# Sch.net
KiCad netlist of a schematic drawn in EAGLE
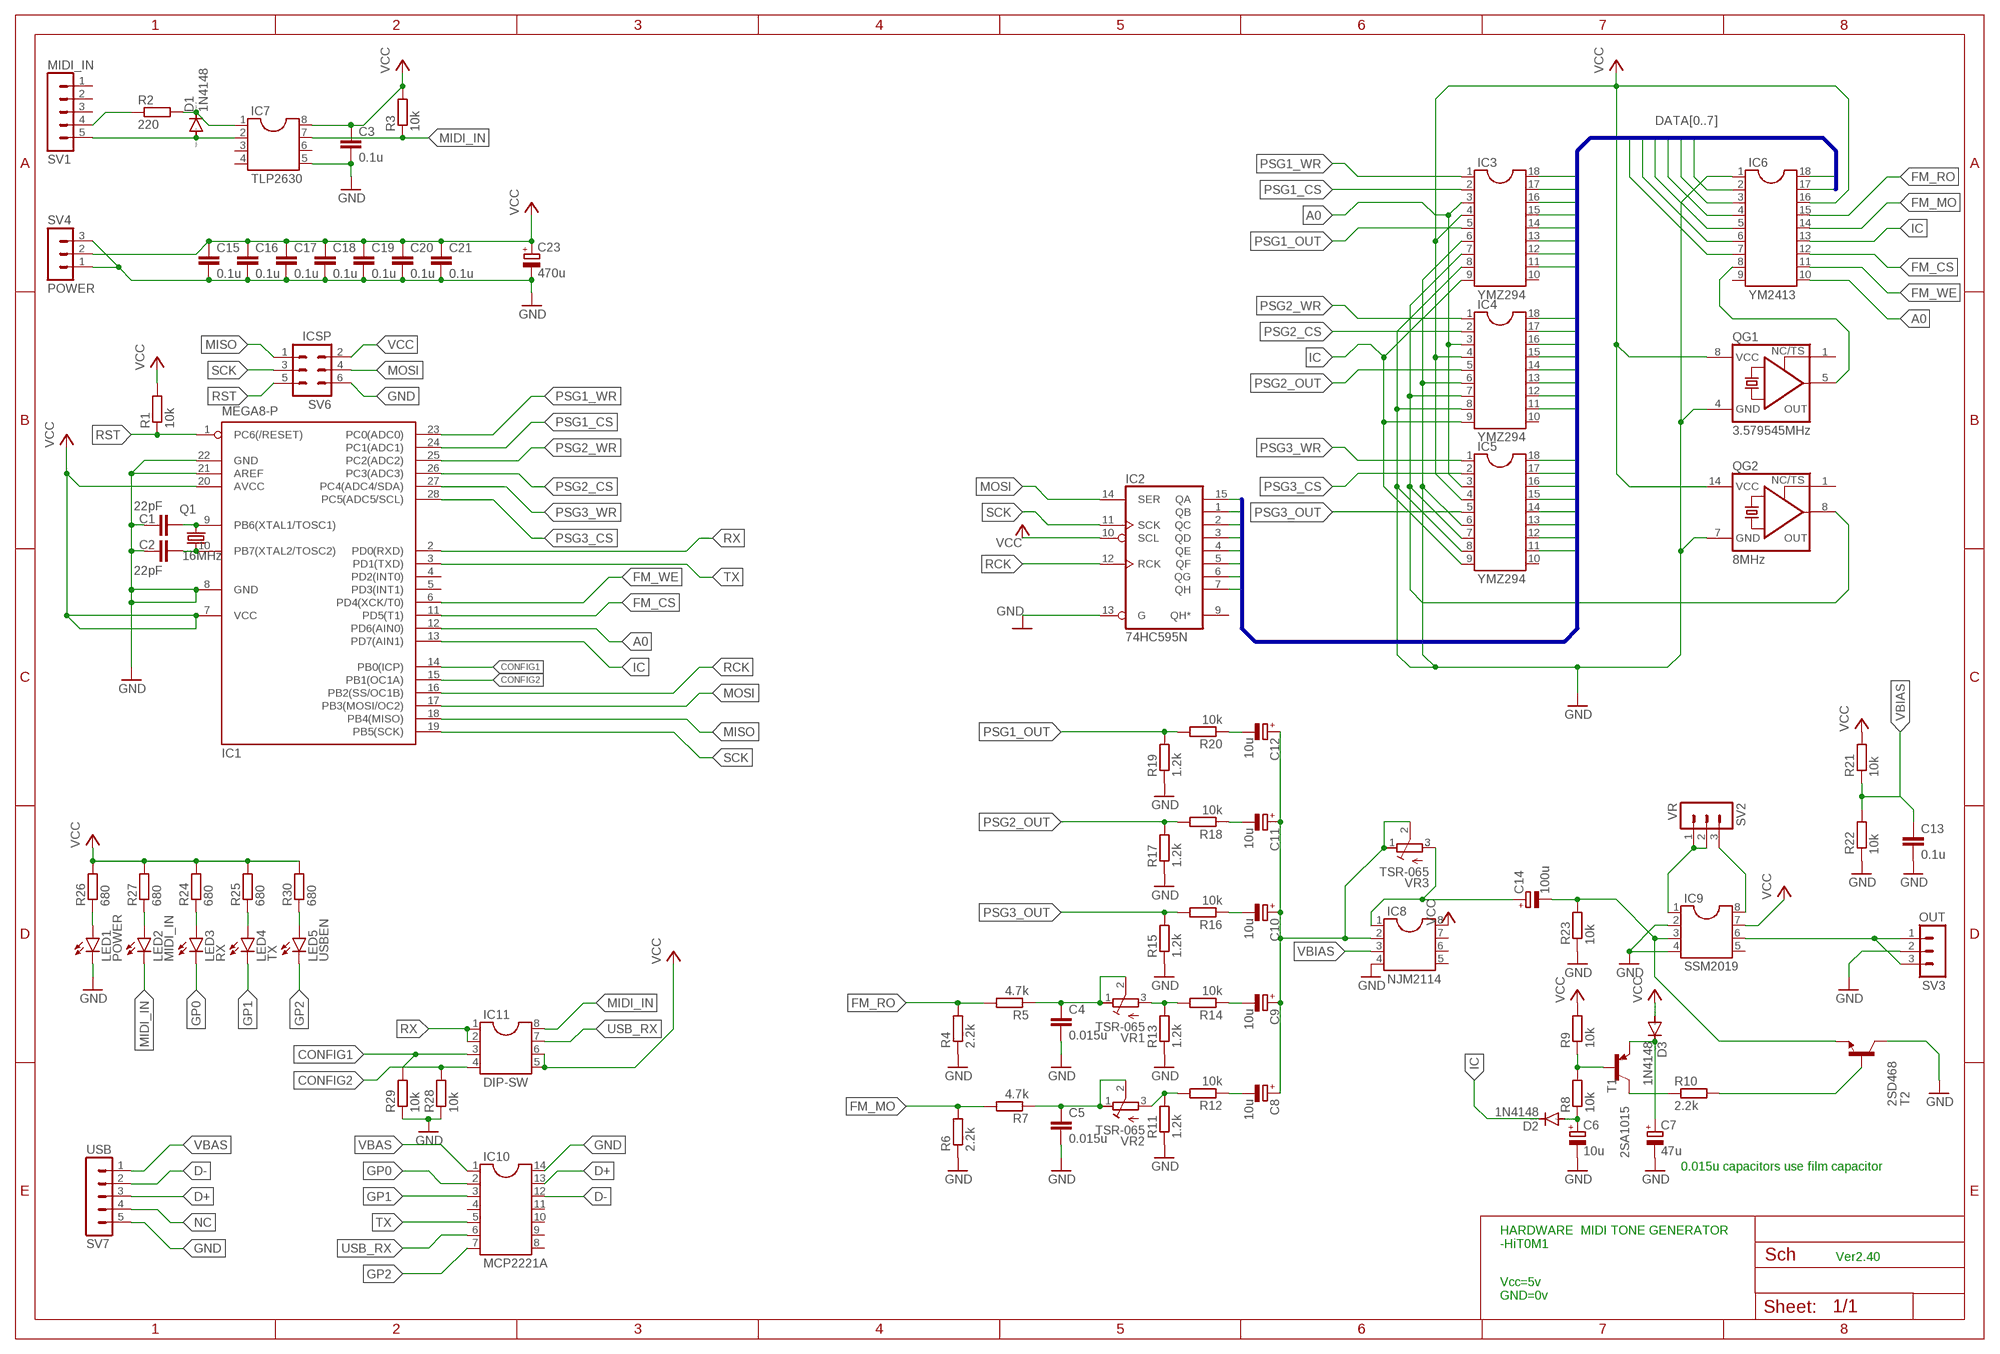
[diagram p0: schematic, sheet 1]

(export (version "E")
  (design (tool "Eeschema 10.0.6"))
  (components
    (comp (ref "C1")
      (value "22pF")
      (footprint "eagle-import:C050-025X075")
      (libsource (lib "eagle-import") (part "C-EU050-025X075"))
    )
    (comp (ref "C2")
      (value "22pF")
      (footprint "eagle-import:C050-025X075")
      (libsource (lib "eagle-import") (part "C-EU050-025X075"))
    )
    (comp (ref "C3")
      (value "0.1u")
      (footprint "eagle-import:C025-030X050")
      (libsource (lib "eagle-import") (part "C-EU025-030X050"))
    )
    (comp (ref "C4")
      (value "0.015u")
      (footprint "eagle-import:C050-025X075")
      (libsource (lib "eagle-import") (part "C-EU050-025X075"))
    )
    (comp (ref "C5")
      (value "0.015u")
      (footprint "eagle-import:C050-025X075")
      (libsource (lib "eagle-import") (part "C-EU050-025X075"))
    )
    (comp (ref "C6")
      (value "10u")
      (footprint "eagle-import:E2,5-5")
      (libsource (lib "eagle-import") (part "CPOL-EUE2.5-5"))
    )
    (comp (ref "C7")
      (value "47u")
      (footprint "eagle-import:E2,5-5")
      (libsource (lib "eagle-import") (part "CPOL-EUE2.5-5"))
    )
    (comp (ref "C8")
      (value "10u")
      (footprint "eagle-import:E2,5-5")
      (libsource (lib "eagle-import") (part "CPOL-EUE2.5-5"))
    )
    (comp (ref "C9")
      (value "10u")
      (footprint "eagle-import:E2,5-5")
      (libsource (lib "eagle-import") (part "CPOL-EUE2.5-5"))
    )
    (comp (ref "C10")
      (value "10u")
      (footprint "eagle-import:E2,5-5")
      (libsource (lib "eagle-import") (part "CPOL-EUE2.5-5"))
    )
    (comp (ref "C11")
      (value "10u")
      (footprint "eagle-import:E2,5-5")
      (libsource (lib "eagle-import") (part "CPOL-EUE2.5-5"))
    )
    (comp (ref "C12")
      (value "10u")
      (footprint "eagle-import:E2,5-5")
      (libsource (lib "eagle-import") (part "CPOL-EUE2.5-5"))
    )
    (comp (ref "C13")
      (value "0.1u")
      (footprint "eagle-import:C025-030X050")
      (libsource (lib "eagle-import") (part "C-EU025-030X050"))
    )
    (comp (ref "C14")
      (value "100u")
      (footprint "eagle-import:E2,5-5")
      (libsource (lib "eagle-import") (part "CPOL-EUE2.5-5"))
    )
    (comp (ref "C15")
      (value "0.1u")
      (footprint "eagle-import:C025-030X050")
      (libsource (lib "eagle-import") (part "C-EU025-030X050"))
    )
    (comp (ref "C16")
      (value "0.1u")
      (footprint "eagle-import:C025-030X050")
      (libsource (lib "eagle-import") (part "C-EU025-030X050"))
    )
    (comp (ref "C17")
      (value "0.1u")
      (footprint "eagle-import:C025-030X050")
      (libsource (lib "eagle-import") (part "C-EU025-030X050"))
    )
    (comp (ref "C18")
      (value "0.1u")
      (footprint "eagle-import:C025-030X050")
      (libsource (lib "eagle-import") (part "C-EU025-030X050"))
    )
    (comp (ref "C19")
      (value "0.1u")
      (footprint "eagle-import:C025-030X050")
      (libsource (lib "eagle-import") (part "C-EU025-030X050"))
    )
    (comp (ref "C20")
      (value "0.1u")
      (footprint "eagle-import:C025-030X050")
      (libsource (lib "eagle-import") (part "C-EU025-030X050"))
    )
    (comp (ref "C21")
      (value "0.1u")
      (footprint "eagle-import:C025-030X050")
      (libsource (lib "eagle-import") (part "C-EU025-030X050"))
    )
    (comp (ref "C23")
      (value "470u")
      (footprint "eagle-import:E2,5-5")
      (libsource (lib "eagle-import") (part "CPOL-EUE2.5-5"))
    )
    (comp (ref "D1")
      (value "1N4148")
      (footprint "eagle-import:DO35-7")
      (libsource (lib "eagle-import") (part "1N4148DO35-7"))
    )
    (comp (ref "D2")
      (value "1N4148")
      (footprint "eagle-import:DO35-7")
      (libsource (lib "eagle-import") (part "1N4148DO35-7"))
    )
    (comp (ref "D3")
      (value "1N4148")
      (footprint "eagle-import:DO35-7")
      (libsource (lib "eagle-import") (part "1N4148DO35-7"))
    )
    (comp (ref "IC1")
      (value "MEGA8-P")
      (footprint "eagle-import:DIL28-3")
      (libsource (lib "eagle-import") (part "MEGA8-P"))
    )
    (comp (ref "IC2")
      (value "74HC595N")
      (footprint "eagle-import:DIL16")
      (libsource (lib "eagle-import") (part "74595NHC"))
    )
    (comp (ref "IC3")
      (value "YMZ294")
      (footprint "eagle-import:SOCKET-18")
      (libsource (lib "eagle-import") (part "DIL18S"))
    )
    (comp (ref "IC4")
      (value "YMZ294")
      (footprint "eagle-import:SOCKET-18")
      (libsource (lib "eagle-import") (part "DIL18S"))
    )
    (comp (ref "IC5")
      (value "YMZ294")
      (footprint "eagle-import:SOCKET-18")
      (libsource (lib "eagle-import") (part "DIL18S"))
    )
    (comp (ref "IC6")
      (value "YM2413")
      (footprint "eagle-import:SOCKET-18")
      (libsource (lib "eagle-import") (part "DIL18S"))
    )
    (comp (ref "IC7")
      (value "TLP2630")
      (footprint "eagle-import:SOCKET-08")
      (libsource (lib "eagle-import") (part "DIL8S"))
    )
    (comp (ref "IC8")
      (value "NJM2114")
      (footprint "eagle-import:SOCKET-08")
      (libsource (lib "eagle-import") (part "DIL8S"))
    )
    (comp (ref "IC9")
      (value "SSM2019")
      (footprint "eagle-import:SOCKET-08")
      (libsource (lib "eagle-import") (part "DIL8S"))
    )
    (comp (ref "IC10")
      (value "MCP2221A")
      (footprint "eagle-import:SOCKET-14")
      (libsource (lib "eagle-import") (part "DIL14S"))
    )
    (comp (ref "IC11")
      (value "DIP-SW")
      (footprint "eagle-import:SOCKET-08")
      (libsource (lib "eagle-import") (part "DIL8S"))
    )
    (comp (ref "LED1")
      (value "POWER")
      (footprint "eagle-import:LED3MM")
      (libsource (lib "eagle-import") (part "LED3MM"))
    )
    (comp (ref "LED2")
      (value "MIDI_IN")
      (footprint "eagle-import:LED3MM")
      (libsource (lib "eagle-import") (part "LED3MM"))
    )
    (comp (ref "LED3")
      (value "RX")
      (footprint "eagle-import:LED3MM")
      (libsource (lib "eagle-import") (part "LED3MM"))
    )
    (comp (ref "LED4")
      (value "TX")
      (footprint "eagle-import:LED3MM")
      (libsource (lib "eagle-import") (part "LED3MM"))
    )
    (comp (ref "LED5")
      (value "USBEN")
      (footprint "eagle-import:LED3MM")
      (libsource (lib "eagle-import") (part "LED3MM"))
    )
    (comp (ref "Q1")
      (value "16MHz")
      (footprint "eagle-import:HC49_S")
      (libsource (lib "eagle-import") (part "CRYSTALHC49S"))
    )
    (comp (ref "QG1")
      (value "3.579545MHz")
      (footprint "eagle-import:DIL08S")
      (libsource (lib "eagle-import") (part "XO-8"))
    )
    (comp (ref "QG2")
      (value "8MHz")
      (footprint "eagle-import:DIL14S")
      (libsource (lib "eagle-import") (part "XO-14"))
    )
    (comp (ref "R1")
      (value "10k")
      (footprint "eagle-import:0207_2V")
      (libsource (lib "eagle-import") (part "R-EU_0207/2V"))
    )
    (comp (ref "R2")
      (value "220")
      (footprint "eagle-import:0207_2V")
      (libsource (lib "eagle-import") (part "R-EU_0207/2V"))
    )
    (comp (ref "R3")
      (value "10k")
      (footprint "eagle-import:0207_2V")
      (libsource (lib "eagle-import") (part "R-EU_0207/2V"))
    )
    (comp (ref "R4")
      (value "2.2k")
      (footprint "eagle-import:0207_2V")
      (libsource (lib "eagle-import") (part "R-EU_0207/2V"))
    )
    (comp (ref "R5")
      (value "4.7k")
      (footprint "eagle-import:0207_2V")
      (libsource (lib "eagle-import") (part "R-EU_0207/2V"))
    )
    (comp (ref "R6")
      (value "2.2k")
      (footprint "eagle-import:0207_2V")
      (libsource (lib "eagle-import") (part "R-EU_0207/2V"))
    )
    (comp (ref "R7")
      (value "4.7k")
      (footprint "eagle-import:0207_2V")
      (libsource (lib "eagle-import") (part "R-EU_0207/2V"))
    )
    (comp (ref "R8")
      (value "10k")
      (footprint "eagle-import:0207_2V")
      (libsource (lib "eagle-import") (part "R-EU_0207/2V"))
    )
    (comp (ref "R9")
      (value "10k")
      (footprint "eagle-import:0207_2V")
      (libsource (lib "eagle-import") (part "R-EU_0207/2V"))
    )
    (comp (ref "R10")
      (value "2.2k")
      (footprint "eagle-import:0207_2V")
      (libsource (lib "eagle-import") (part "R-EU_0207/2V"))
    )
    (comp (ref "R11")
      (value "1.2k")
      (footprint "eagle-import:0207_2V")
      (libsource (lib "eagle-import") (part "R-EU_0207/2V"))
    )
    (comp (ref "R12")
      (value "10k")
      (footprint "eagle-import:0207_2V")
      (libsource (lib "eagle-import") (part "R-EU_0207/2V"))
    )
    (comp (ref "R13")
      (value "1.2k")
      (footprint "eagle-import:0207_2V")
      (libsource (lib "eagle-import") (part "R-EU_0207/2V"))
    )
    (comp (ref "R14")
      (value "10k")
      (footprint "eagle-import:0207_2V")
      (libsource (lib "eagle-import") (part "R-EU_0207/2V"))
    )
    (comp (ref "R15")
      (value "1.2k")
      (footprint "eagle-import:0207_2V")
      (libsource (lib "eagle-import") (part "R-EU_0207/2V"))
    )
    (comp (ref "R16")
      (value "10k")
      (footprint "eagle-import:0207_2V")
      (libsource (lib "eagle-import") (part "R-EU_0207/2V"))
    )
    (comp (ref "R17")
      (value "1.2k")
      (footprint "eagle-import:0207_2V")
      (libsource (lib "eagle-import") (part "R-EU_0207/2V"))
    )
    (comp (ref "R18")
      (value "10k")
      (footprint "eagle-import:0207_2V")
      (libsource (lib "eagle-import") (part "R-EU_0207/2V"))
    )
    (comp (ref "R19")
      (value "1.2k")
      (footprint "eagle-import:0207_2V")
      (libsource (lib "eagle-import") (part "R-EU_0207/2V"))
    )
    (comp (ref "R20")
      (value "10k")
      (footprint "eagle-import:0207_2V")
      (libsource (lib "eagle-import") (part "R-EU_0207/2V"))
    )
    (comp (ref "R21")
      (value "10k")
      (footprint "eagle-import:0207_2V")
      (libsource (lib "eagle-import") (part "R-EU_0207/2V"))
    )
    (comp (ref "R22")
      (value "10k")
      (footprint "eagle-import:0207_2V")
      (libsource (lib "eagle-import") (part "R-EU_0207/2V"))
    )
    (comp (ref "R23")
      (value "10k")
      (footprint "eagle-import:0207_2V")
      (libsource (lib "eagle-import") (part "R-EU_0207/2V"))
    )
    (comp (ref "R24")
      (value "680")
      (footprint "eagle-import:0207_2V")
      (libsource (lib "eagle-import") (part "R-EU_0207/2V"))
    )
    (comp (ref "R25")
      (value "680")
      (footprint "eagle-import:0207_2V")
      (libsource (lib "eagle-import") (part "R-EU_0207/2V"))
    )
    (comp (ref "R26")
      (value "680")
      (footprint "eagle-import:0207_2V")
      (libsource (lib "eagle-import") (part "R-EU_0207/2V"))
    )
    (comp (ref "R27")
      (value "680")
      (footprint "eagle-import:0207_2V")
      (libsource (lib "eagle-import") (part "R-EU_0207/2V"))
    )
    (comp (ref "R28")
      (value "10k")
      (footprint "eagle-import:0207_2V")
      (libsource (lib "eagle-import") (part "R-EU_0207/2V"))
    )
    (comp (ref "R29")
      (value "10k")
      (footprint "eagle-import:0207_2V")
      (libsource (lib "eagle-import") (part "R-EU_0207/2V"))
    )
    (comp (ref "R30")
      (value "680")
      (footprint "eagle-import:0207_2V")
      (libsource (lib "eagle-import") (part "R-EU_0207/2V"))
    )
    (comp (ref "SV1")
      (value "MIDI_IN")
      (footprint "eagle-import:MA05-1")
      (libsource (lib "eagle-import") (part "MA05-1"))
    )
    (comp (ref "SV2")
      (value "VR")
      (footprint "eagle-import:MA03-1")
      (libsource (lib "eagle-import") (part "MA03-1"))
    )
    (comp (ref "SV3")
      (value "OUT")
      (footprint "eagle-import:MA03-1")
      (libsource (lib "eagle-import") (part "MA03-1"))
    )
    (comp (ref "SV4")
      (value "POWER")
      (footprint "eagle-import:MA03-1")
      (libsource (lib "eagle-import") (part "MA03-1"))
    )
    (comp (ref "SV6")
      (value "ICSP")
      (footprint "eagle-import:MA03-2")
      (libsource (lib "eagle-import") (part "MA03-2"))
    )
    (comp (ref "SV7")
      (value "USB")
      (footprint "eagle-import:MA05-1")
      (libsource (lib "eagle-import") (part "MA05-1"))
    )
    (comp (ref "T1")
      (value "2SA1015")
      (footprint "eagle-import:TO92")
      (libsource (lib "eagle-import") (part "-PNP-TO92"))
    )
    (comp (ref "T2")
      (value "2SD468")
      (footprint "eagle-import:TO92")
      (libsource (lib "eagle-import") (part "-NPN-TO92"))
    )
    (comp (ref "VR1")
      (value "TSR-065")
      (footprint "eagle-import:TSR-065")
      (libsource (lib "eagle-import") (part "TSR-065"))
    )
    (comp (ref "VR2")
      (value "TSR-065")
      (footprint "eagle-import:TSR-065")
      (libsource (lib "eagle-import") (part "TSR-065"))
    )
    (comp (ref "VR3")
      (value "TSR-065")
      (footprint "eagle-import:TSR-065")
      (libsource (lib "eagle-import") (part "TSR-065"))
    )
  )
  (nets
    (net (code "1") (name "/DATA0") (class "Default")
      (node (ref "IC2") (pin "15") (pinfunction "QA_15") (pintype "tri_state"))
      (node (ref "IC3") (pin "18") (pinfunction "18_18") (pintype "passive"))
      (node (ref "IC4") (pin "18") (pinfunction "18_18") (pintype "passive"))
      (node (ref "IC5") (pin "18") (pinfunction "18_18") (pintype "passive"))
      (node (ref "IC6") (pin "17") (pinfunction "17_17") (pintype "passive"))
    )
    (net (code "2") (name "/DATA1") (class "Default")
      (node (ref "IC2") (pin "1") (pinfunction "QB_1") (pintype "tri_state"))
      (node (ref "IC3") (pin "17") (pinfunction "17_17") (pintype "passive"))
      (node (ref "IC4") (pin "17") (pinfunction "17_17") (pintype "passive"))
      (node (ref "IC5") (pin "17") (pinfunction "17_17") (pintype "passive"))
      (node (ref "IC6") (pin "18") (pinfunction "18_18") (pintype "passive"))
    )
    (net (code "3") (name "/DATA2") (class "Default")
      (node (ref "IC2") (pin "2") (pinfunction "QC_2") (pintype "tri_state"))
      (node (ref "IC3") (pin "16") (pinfunction "16_16") (pintype "passive"))
      (node (ref "IC4") (pin "16") (pinfunction "16_16") (pintype "passive"))
      (node (ref "IC5") (pin "16") (pinfunction "16_16") (pintype "passive"))
      (node (ref "IC6") (pin "2") (pinfunction "2_2") (pintype "passive"))
    )
    (net (code "4") (name "/DATA3") (class "Default")
      (node (ref "IC2") (pin "3") (pinfunction "QD_3") (pintype "tri_state"))
      (node (ref "IC3") (pin "15") (pinfunction "15_15") (pintype "passive"))
      (node (ref "IC4") (pin "15") (pinfunction "15_15") (pintype "passive"))
      (node (ref "IC5") (pin "15") (pinfunction "15_15") (pintype "passive"))
      (node (ref "IC6") (pin "3") (pinfunction "3_3") (pintype "passive"))
    )
    (net (code "5") (name "/DATA4") (class "Default")
      (node (ref "IC2") (pin "4") (pinfunction "QE_4") (pintype "tri_state"))
      (node (ref "IC3") (pin "14") (pinfunction "14_14") (pintype "passive"))
      (node (ref "IC4") (pin "14") (pinfunction "14_14") (pintype "passive"))
      (node (ref "IC5") (pin "14") (pinfunction "14_14") (pintype "passive"))
      (node (ref "IC6") (pin "4") (pinfunction "4_4") (pintype "passive"))
    )
    (net (code "6") (name "/DATA5") (class "Default")
      (node (ref "IC2") (pin "5") (pinfunction "QF_5") (pintype "tri_state"))
      (node (ref "IC3") (pin "13") (pinfunction "13_13") (pintype "passive"))
      (node (ref "IC4") (pin "13") (pinfunction "13_13") (pintype "passive"))
      (node (ref "IC5") (pin "13") (pinfunction "13_13") (pintype "passive"))
      (node (ref "IC6") (pin "5") (pinfunction "5_5") (pintype "passive"))
    )
    (net (code "7") (name "/DATA6") (class "Default")
      (node (ref "IC2") (pin "6") (pinfunction "QG_6") (pintype "tri_state"))
      (node (ref "IC3") (pin "12") (pinfunction "12_12") (pintype "passive"))
      (node (ref "IC4") (pin "12") (pinfunction "12_12") (pintype "passive"))
      (node (ref "IC5") (pin "12") (pinfunction "12_12") (pintype "passive"))
      (node (ref "IC6") (pin "6") (pinfunction "6_6") (pintype "passive"))
    )
    (net (code "8") (name "/DATA7") (class "Default")
      (node (ref "IC2") (pin "7") (pinfunction "QH_7") (pintype "tri_state"))
      (node (ref "IC3") (pin "11") (pinfunction "11_11") (pintype "passive"))
      (node (ref "IC4") (pin "11") (pinfunction "11_11") (pintype "passive"))
      (node (ref "IC5") (pin "11") (pinfunction "11_11") (pintype "passive"))
      (node (ref "IC6") (pin "7") (pinfunction "7_7") (pintype "passive"))
    )
    (net (code "10") (name "A0") (class "Default")
      (node (ref "IC1") (pin "12") (pinfunction "PD6(AIN0)_12") (pintype "bidirectional"))
      (node (ref "IC3") (pin "3") (pinfunction "3_3") (pintype "passive"))
      (node (ref "IC4") (pin "3") (pinfunction "3_3") (pintype "passive"))
      (node (ref "IC5") (pin "3") (pinfunction "3_3") (pintype "passive"))
      (node (ref "IC6") (pin "10") (pinfunction "10_10") (pintype "passive"))
    )
    (net (code "11") (name "CONFIG1") (class "Default")
      (node (ref "IC1") (pin "14") (pinfunction "PB0(ICP)_14") (pintype "bidirectional"))
      (node (ref "IC11") (pin "3") (pinfunction "3_3") (pintype "passive"))
      (node (ref "R29") (pin "2") (pinfunction "2_2") (pintype "passive"))
    )
    (net (code "12") (name "CONFIG2") (class "Default")
      (node (ref "IC1") (pin "15") (pinfunction "PB1(OC1A)_15") (pintype "bidirectional"))
      (node (ref "IC11") (pin "4") (pinfunction "4_4") (pintype "passive"))
      (node (ref "R28") (pin "2") (pinfunction "2_2") (pintype "passive"))
    )
    (net (code "13") (name "D+") (class "Default")
      (node (ref "IC10") (pin "13") (pinfunction "13_13") (pintype "passive"))
      (node (ref "SV7") (pin "3") (pinfunction "3_3") (pintype "passive"))
    )
    (net (code "14") (name "D-") (class "Default")
      (node (ref "IC10") (pin "12") (pinfunction "12_12") (pintype "passive"))
      (node (ref "SV7") (pin "2") (pinfunction "2_2") (pintype "passive"))
    )
    (net (code "15") (name "FM_CS") (class "Default")
      (node (ref "IC1") (pin "11") (pinfunction "PD5(T1)_11") (pintype "bidirectional"))
      (node (ref "IC6") (pin "12") (pinfunction "12_12") (pintype "passive"))
    )
    (net (code "16") (name "FM_MO") (class "Default")
      (node (ref "IC6") (pin "14") (pinfunction "14_14") (pintype "passive"))
      (node (ref "R6") (pin "2") (pinfunction "2_2") (pintype "passive"))
      (node (ref "R7") (pin "2") (pinfunction "2_2") (pintype "passive"))
    )
    (net (code "17") (name "FM_RO") (class "Default")
      (node (ref "IC6") (pin "15") (pinfunction "15_15") (pintype "passive"))
      (node (ref "R4") (pin "2") (pinfunction "2_2") (pintype "passive"))
      (node (ref "R5") (pin "2") (pinfunction "2_2") (pintype "passive"))
    )
    (net (code "18") (name "FM_WE") (class "Default")
      (node (ref "IC1") (pin "6") (pinfunction "PD4(XCK/T0)_6") (pintype "bidirectional"))
      (node (ref "IC6") (pin "11") (pinfunction "11_11") (pintype "passive"))
    )
    (net (code "19") (name "GND") (class "Default")
      (node (ref "C1") (pin "2") (pinfunction "2_2") (pintype "passive"))
      (node (ref "C13") (pin "2") (pinfunction "2_2") (pintype "passive"))
      (node (ref "C15") (pin "2") (pinfunction "2_2") (pintype "passive"))
      (node (ref "C16") (pin "2") (pinfunction "2_2") (pintype "passive"))
      (node (ref "C17") (pin "2") (pinfunction "2_2") (pintype "passive"))
      (node (ref "C18") (pin "2") (pinfunction "2_2") (pintype "passive"))
      (node (ref "C19") (pin "2") (pinfunction "2_2") (pintype "passive"))
      (node (ref "C2") (pin "2") (pinfunction "2_2") (pintype "passive"))
      (node (ref "C20") (pin "2") (pinfunction "2_2") (pintype "passive"))
      (node (ref "C21") (pin "2") (pinfunction "2_2") (pintype "passive"))
      (node (ref "C23") (pin "-") (pinfunction "-_-") (pintype "passive"))
      (node (ref "C3") (pin "2") (pinfunction "2_2") (pintype "passive"))
      (node (ref "C4") (pin "2") (pinfunction "2_2") (pintype "passive"))
      (node (ref "C5") (pin "2") (pinfunction "2_2") (pintype "passive"))
      (node (ref "C6") (pin "-") (pinfunction "-_-") (pintype "passive"))
      (node (ref "C7") (pin "-") (pinfunction "-_-") (pintype "passive"))
      (node (ref "IC1") (pin "21") (pinfunction "AREF_21") (pintype "passive"))
      (node (ref "IC1") (pin "22") (pinfunction "GND_22") (pintype "power_in"))
      (node (ref "IC1") (pin "8") (pinfunction "GND_8") (pintype "power_in"))
      (node (ref "IC10") (pin "14") (pinfunction "14_14") (pintype "passive"))
      (node (ref "IC2") (pin "13") (pinfunction "G_13") (pintype "input"))
      (node (ref "IC3") (pin "6") (pinfunction "6_6") (pintype "passive"))
      (node (ref "IC3") (pin "8") (pinfunction "8_8") (pintype "passive"))
      (node (ref "IC4") (pin "6") (pinfunction "6_6") (pintype "passive"))
      (node (ref "IC4") (pin "8") (pinfunction "8_8") (pintype "passive"))
      (node (ref "IC5") (pin "6") (pinfunction "6_6") (pintype "passive"))
      (node (ref "IC5") (pin "8") (pinfunction "8_8") (pintype "passive"))
      (node (ref "IC6") (pin "1") (pinfunction "1_1") (pintype "passive"))
      (node (ref "IC7") (pin "5") (pinfunction "5_5") (pintype "passive"))
      (node (ref "IC8") (pin "4") (pinfunction "4_4") (pintype "passive"))
      (node (ref "IC9") (pin "2") (pinfunction "2_2") (pintype "passive"))
      (node (ref "IC9") (pin "4") (pinfunction "4_4") (pintype "passive"))
      (node (ref "LED1") (pin "K") (pinfunction "C_K") (pintype "passive"))
      (node (ref "QG1") (pin "4") (pinfunction "GND_4") (pintype "power_in"))
      (node (ref "QG2") (pin "7") (pinfunction "GND_7") (pintype "power_in"))
      (node (ref "R11") (pin "1") (pinfunction "1_1") (pintype "passive"))
      (node (ref "R13") (pin "1") (pinfunction "1_1") (pintype "passive"))
      (node (ref "R15") (pin "1") (pinfunction "1_1") (pintype "passive"))
      (node (ref "R17") (pin "1") (pinfunction "1_1") (pintype "passive"))
      (node (ref "R19") (pin "1") (pinfunction "1_1") (pintype "passive"))
      (node (ref "R22") (pin "1") (pinfunction "1_1") (pintype "passive"))
      (node (ref "R23") (pin "1") (pinfunction "1_1") (pintype "passive"))
      (node (ref "R28") (pin "1") (pinfunction "1_1") (pintype "passive"))
      (node (ref "R29") (pin "1") (pinfunction "1_1") (pintype "passive"))
      (node (ref "R4") (pin "1") (pinfunction "1_1") (pintype "passive"))
      (node (ref "R6") (pin "1") (pinfunction "1_1") (pintype "passive"))
      (node (ref "SV3") (pin "2") (pinfunction "2_2") (pintype "passive"))
      (node (ref "SV4") (pin "1") (pinfunction "1_1") (pintype "passive"))
      (node (ref "SV4") (pin "3") (pinfunction "3_3") (pintype "passive"))
      (node (ref "SV6") (pin "6") (pinfunction "6_6") (pintype "passive"))
      (node (ref "SV7") (pin "5") (pinfunction "5_5") (pintype "passive"))
      (node (ref "T2") (pin "3") (pinfunction "C_3") (pintype "passive"))
    )
    (net (code "20") (name "GP0") (class "Default")
      (node (ref "IC10") (pin "2") (pinfunction "2_2") (pintype "passive"))
      (node (ref "LED3") (pin "K") (pinfunction "C_K") (pintype "passive"))
    )
    (net (code "21") (name "GP1") (class "Default")
      (node (ref "IC10") (pin "3") (pinfunction "3_3") (pintype "passive"))
      (node (ref "LED4") (pin "K") (pinfunction "C_K") (pintype "passive"))
    )
    (net (code "22") (name "GP2") (class "Default")
      (node (ref "IC10") (pin "7") (pinfunction "7_7") (pintype "passive"))
      (node (ref "LED5") (pin "K") (pinfunction "C_K") (pintype "passive"))
    )
    (net (code "23") (name "IC") (class "Default")
      (node (ref "D2") (pin "C") (pinfunction "C_C") (pintype "passive"))
      (node (ref "IC1") (pin "13") (pinfunction "PD7(AIN1)_13") (pintype "bidirectional"))
      (node (ref "IC3") (pin "9") (pinfunction "9_9") (pintype "passive"))
      (node (ref "IC4") (pin "9") (pinfunction "9_9") (pintype "passive"))
      (node (ref "IC5") (pin "9") (pinfunction "9_9") (pintype "passive"))
      (node (ref "IC6") (pin "13") (pinfunction "13_13") (pintype "passive"))
    )
    (net (code "24") (name "MIDI_IN") (class "Default")
      (node (ref "IC11") (pin "8") (pinfunction "8_8") (pintype "passive"))
      (node (ref "IC7") (pin "7") (pinfunction "7_7") (pintype "passive"))
      (node (ref "LED2") (pin "K") (pinfunction "C_K") (pintype "passive"))
      (node (ref "R3") (pin "1") (pinfunction "1_1") (pintype "passive"))
    )
    (net (code "25") (name "MISO") (class "Default")
      (node (ref "IC1") (pin "18") (pinfunction "PB4(MISO)_18") (pintype "bidirectional"))
      (node (ref "SV6") (pin "1") (pinfunction "1_1") (pintype "passive"))
    )
    (net (code "26") (name "MOSI") (class "Default")
      (node (ref "IC1") (pin "17") (pinfunction "PB3(MOSI/OC2)_17") (pintype "bidirectional"))
      (node (ref "IC2") (pin "14") (pinfunction "SER_14") (pintype "input"))
      (node (ref "SV6") (pin "4") (pinfunction "4_4") (pintype "passive"))
    )
    (net (code "27") (name "NC") (class "Default")
      (node (ref "SV7") (pin "4") (pinfunction "4_4") (pintype "passive"))
    )
    (net (code "28") (name "Net-(C6-Pad+)") (class "Default")
      (node (ref "C6") (pin "+") (pinfunction "+_+") (pintype "passive"))
      (node (ref "D2") (pin "A") (pinfunction "A_A") (pintype "passive"))
      (node (ref "R8") (pin "1") (pinfunction "1_1") (pintype "passive"))
    )
    (net (code "29") (name "Net-(C8-Pad-)") (class "Default")
      (node (ref "C8") (pin "-") (pinfunction "-_-") (pintype "passive"))
      (node (ref "R12") (pin "1") (pinfunction "1_1") (pintype "passive"))
    )
    (net (code "30") (name "Net-(C9-Pad-)") (class "Default")
      (node (ref "C9") (pin "-") (pinfunction "-_-") (pintype "passive"))
      (node (ref "R14") (pin "1") (pinfunction "1_1") (pintype "passive"))
    )
    (net (code "31") (name "Net-(C10-Pad-)") (class "Default")
      (node (ref "C10") (pin "-") (pinfunction "-_-") (pintype "passive"))
      (node (ref "R16") (pin "1") (pinfunction "1_1") (pintype "passive"))
    )
    (net (code "32") (name "Net-(C11-Pad-)") (class "Default")
      (node (ref "C11") (pin "-") (pinfunction "-_-") (pintype "passive"))
      (node (ref "R18") (pin "1") (pinfunction "1_1") (pintype "passive"))
    )
    (net (code "33") (name "Net-(C12-Pad-)") (class "Default")
      (node (ref "C12") (pin "-") (pinfunction "-_-") (pintype "passive"))
      (node (ref "R20") (pin "1") (pinfunction "1_1") (pintype "passive"))
    )
    (net (code "34") (name "Net-(D1-PadA)") (class "Default")
      (node (ref "D1") (pin "A") (pinfunction "A_A") (pintype "passive"))
      (node (ref "IC7") (pin "2") (pinfunction "2_2") (pintype "passive"))
      (node (ref "SV1") (pin "5") (pinfunction "5_5") (pintype "passive"))
    )
    (net (code "35") (name "Net-(D1-PadC)") (class "Default")
      (node (ref "D1") (pin "C") (pinfunction "C_C") (pintype "passive"))
      (node (ref "IC7") (pin "1") (pinfunction "1_1") (pintype "passive"))
      (node (ref "R2") (pin "2") (pinfunction "2_2") (pintype "passive"))
    )
    (net (code "36") (name "Net-(IC1-PB6(XTAL1{slash}TOSC1))") (class "Default")
      (node (ref "C1") (pin "1") (pinfunction "1_1") (pintype "passive"))
      (node (ref "IC1") (pin "9") (pinfunction "PB6(XTAL1/TOSC1)_9") (pintype "bidirectional"))
      (node (ref "Q1") (pin "2") (pinfunction "2_2") (pintype "passive"))
    )
    (net (code "37") (name "Net-(IC1-PB7(XTAL2{slash}TOSC2))") (class "Default")
      (node (ref "C2") (pin "1") (pinfunction "1_1") (pintype "passive"))
      (node (ref "IC1") (pin "10") (pinfunction "PB7(XTAL2/TOSC2)_10") (pintype "bidirectional"))
      (node (ref "Q1") (pin "1") (pinfunction "1_1") (pintype "passive"))
    )
    (net (code "38") (name "Net-(IC9-Pad1)") (class "Default")
      (node (ref "IC9") (pin "1") (pinfunction "1_1") (pintype "passive"))
      (node (ref "SV2") (pin "1") (pinfunction "1_1") (pintype "passive"))
      (node (ref "SV2") (pin "2") (pinfunction "2_2") (pintype "passive"))
    )
    (net (code "39") (name "Net-(IC9-Pad6)") (class "Default")
      (node (ref "IC9") (pin "6") (pinfunction "6_6") (pintype "passive"))
      (node (ref "SV3") (pin "1") (pinfunction "1_1") (pintype "passive"))
      (node (ref "SV3") (pin "3") (pinfunction "3_3") (pintype "passive"))
    )
    (net (code "40") (name "Net-(IC9-Pad8)") (class "Default")
      (node (ref "IC9") (pin "8") (pinfunction "8_8") (pintype "passive"))
      (node (ref "SV2") (pin "3") (pinfunction "3_3") (pintype "passive"))
    )
    (net (code "41") (name "Net-(LED1-PadA)") (class "Default")
      (node (ref "LED1") (pin "A") (pinfunction "A_A") (pintype "passive"))
      (node (ref "R26") (pin "1") (pinfunction "1_1") (pintype "passive"))
    )
    (net (code "42") (name "Net-(LED2-PadA)") (class "Default")
      (node (ref "LED2") (pin "A") (pinfunction "A_A") (pintype "passive"))
      (node (ref "R27") (pin "1") (pinfunction "1_1") (pintype "passive"))
    )
    (net (code "43") (name "Net-(LED3-PadA)") (class "Default")
      (node (ref "LED3") (pin "A") (pinfunction "A_A") (pintype "passive"))
      (node (ref "R24") (pin "1") (pinfunction "1_1") (pintype "passive"))
    )
    (net (code "44") (name "Net-(LED4-PadA)") (class "Default")
      (node (ref "LED4") (pin "A") (pinfunction "A_A") (pintype "passive"))
      (node (ref "R25") (pin "1") (pinfunction "1_1") (pintype "passive"))
    )
    (net (code "45") (name "Net-(LED5-PadA)") (class "Default")
      (node (ref "LED5") (pin "A") (pinfunction "A_A") (pintype "passive"))
      (node (ref "R30") (pin "1") (pinfunction "1_1") (pintype "passive"))
    )
    (net (code "46") (name "Net-(QG1-OUT)") (class "Default")
      (node (ref "IC6") (pin "8") (pinfunction "8_8") (pintype "passive"))
      (node (ref "QG1") (pin "5") (pinfunction "OUT_5") (pintype "output"))
    )
    (net (code "47") (name "Net-(QG2-OUT)") (class "Default")
      (node (ref "IC3") (pin "7") (pinfunction "7_7") (pintype "passive"))
      (node (ref "IC4") (pin "7") (pinfunction "7_7") (pintype "passive"))
      (node (ref "IC5") (pin "7") (pinfunction "7_7") (pintype "passive"))
      (node (ref "QG2") (pin "8") (pinfunction "OUT_8") (pintype "output"))
    )
    (net (code "48") (name "Net-(R2-Pad1)") (class "Default")
      (node (ref "R2") (pin "1") (pinfunction "1_1") (pintype "passive"))
      (node (ref "SV1") (pin "4") (pinfunction "4_4") (pintype "passive"))
    )
    (net (code "49") (name "Net-(T1-B)") (class "Default")
      (node (ref "R8") (pin "2") (pinfunction "2_2") (pintype "passive"))
      (node (ref "R9") (pin "1") (pinfunction "1_1") (pintype "passive"))
      (node (ref "T1") (pin "2") (pinfunction "B_2") (pintype "passive"))
    )
    (net (code "50") (name "Net-(T1-C)") (class "Default")
      (node (ref "R10") (pin "1") (pinfunction "1_1") (pintype "passive"))
      (node (ref "T1") (pin "3") (pinfunction "C_3") (pintype "passive"))
    )
    (net (code "51") (name "Net-(T1-E)") (class "Default")
      (node (ref "C7") (pin "+") (pinfunction "+_+") (pintype "passive"))
      (node (ref "D3") (pin "C") (pinfunction "C_C") (pintype "passive"))
      (node (ref "T1") (pin "1") (pinfunction "E_1") (pintype "passive"))
    )
    (net (code "52") (name "Net-(T2-B)") (class "Default")
      (node (ref "R10") (pin "2") (pinfunction "2_2") (pintype "passive"))
      (node (ref "T2") (pin "2") (pinfunction "B_2") (pintype "passive"))
    )
    (net (code "53") (name "Net-(T2-E)") (class "Default")
      (node (ref "C14") (pin "-") (pinfunction "-_-") (pintype "passive"))
      (node (ref "IC9") (pin "3") (pinfunction "3_3") (pintype "passive"))
      (node (ref "R23") (pin "2") (pinfunction "2_2") (pintype "passive"))
      (node (ref "T2") (pin "1") (pinfunction "E_1") (pintype "passive"))
    )
    (net (code "54") (name "Net-(VR1-A)") (class "Default")
      (node (ref "C4") (pin "1") (pinfunction "1_1") (pintype "passive"))
      (node (ref "R5") (pin "1") (pinfunction "1_1") (pintype "passive"))
      (node (ref "VR1") (pin "1") (pinfunction "A_1") (pintype "passive"))
      (node (ref "VR1") (pin "2") (pinfunction "S_2") (pintype "passive"))
    )
    (net (code "55") (name "Net-(VR1-E)") (class "Default")
      (node (ref "R13") (pin "2") (pinfunction "2_2") (pintype "passive"))
      (node (ref "R14") (pin "2") (pinfunction "2_2") (pintype "passive"))
      (node (ref "VR1") (pin "3") (pinfunction "E_3") (pintype "passive"))
    )
    (net (code "56") (name "Net-(VR2-A)") (class "Default")
      (node (ref "C5") (pin "1") (pinfunction "1_1") (pintype "passive"))
      (node (ref "R7") (pin "1") (pinfunction "1_1") (pintype "passive"))
      (node (ref "VR2") (pin "1") (pinfunction "A_1") (pintype "passive"))
      (node (ref "VR2") (pin "2") (pinfunction "S_2") (pintype "passive"))
    )
    (net (code "57") (name "Net-(VR2-E)") (class "Default")
      (node (ref "R11") (pin "2") (pinfunction "2_2") (pintype "passive"))
      (node (ref "R12") (pin "2") (pinfunction "2_2") (pintype "passive"))
      (node (ref "VR2") (pin "3") (pinfunction "E_3") (pintype "passive"))
    )
    (net (code "58") (name "Net-(VR3-A)") (class "Default")
      (node (ref "C10") (pin "+") (pinfunction "+_+") (pintype "passive"))
      (node (ref "C11") (pin "+") (pinfunction "+_+") (pintype "passive"))
      (node (ref "C12") (pin "+") (pinfunction "+_+") (pintype "passive"))
      (node (ref "C8") (pin "+") (pinfunction "+_+") (pintype "passive"))
      (node (ref "C9") (pin "+") (pinfunction "+_+") (pintype "passive"))
      (node (ref "IC8") (pin "2") (pinfunction "2_2") (pintype "passive"))
      (node (ref "VR3") (pin "1") (pinfunction "A_1") (pintype "passive"))
      (node (ref "VR3") (pin "2") (pinfunction "S_2") (pintype "passive"))
    )
    (net (code "59") (name "Net-(VR3-E)") (class "Default")
      (node (ref "C14") (pin "+") (pinfunction "+_+") (pintype "passive"))
      (node (ref "IC8") (pin "1") (pinfunction "1_1") (pintype "passive"))
      (node (ref "VR3") (pin "3") (pinfunction "E_3") (pintype "passive"))
    )
    (net (code "60") (name "PSG1_CS") (class "Default")
      (node (ref "IC1") (pin "24") (pinfunction "PC1(ADC1)_24") (pintype "bidirectional"))
      (node (ref "IC3") (pin "2") (pinfunction "2_2") (pintype "passive"))
    )
    (net (code "61") (name "PSG1_OUT") (class "Default")
      (node (ref "IC3") (pin "5") (pinfunction "5_5") (pintype "passive"))
      (node (ref "R19") (pin "2") (pinfunction "2_2") (pintype "passive"))
      (node (ref "R20") (pin "2") (pinfunction "2_2") (pintype "passive"))
    )
    (net (code "62") (name "PSG1_WR") (class "Default")
      (node (ref "IC1") (pin "23") (pinfunction "PC0(ADC0)_23") (pintype "bidirectional"))
      (node (ref "IC3") (pin "1") (pinfunction "1_1") (pintype "passive"))
    )
    (net (code "63") (name "PSG2_CS") (class "Default")
      (node (ref "IC1") (pin "26") (pinfunction "PC3(ADC3)_26") (pintype "bidirectional"))
      (node (ref "IC4") (pin "2") (pinfunction "2_2") (pintype "passive"))
    )
    (net (code "64") (name "PSG2_OUT") (class "Default")
      (node (ref "IC4") (pin "5") (pinfunction "5_5") (pintype "passive"))
      (node (ref "R17") (pin "2") (pinfunction "2_2") (pintype "passive"))
      (node (ref "R18") (pin "2") (pinfunction "2_2") (pintype "passive"))
    )
    (net (code "65") (name "PSG2_WR") (class "Default")
      (node (ref "IC1") (pin "25") (pinfunction "PC2(ADC2)_25") (pintype "bidirectional"))
      (node (ref "IC4") (pin "1") (pinfunction "1_1") (pintype "passive"))
    )
    (net (code "66") (name "PSG3_CS") (class "Default")
      (node (ref "IC1") (pin "28") (pinfunction "PC5(ADC5/SCL)_28") (pintype "bidirectional"))
      (node (ref "IC5") (pin "2") (pinfunction "2_2") (pintype "passive"))
    )
    (net (code "67") (name "PSG3_OUT") (class "Default")
      (node (ref "IC5") (pin "5") (pinfunction "5_5") (pintype "passive"))
      (node (ref "R15") (pin "2") (pinfunction "2_2") (pintype "passive"))
      (node (ref "R16") (pin "2") (pinfunction "2_2") (pintype "passive"))
    )
    (net (code "68") (name "PSG3_WR") (class "Default")
      (node (ref "IC1") (pin "27") (pinfunction "PC4(ADC4/SDA)_27") (pintype "bidirectional"))
      (node (ref "IC5") (pin "1") (pinfunction "1_1") (pintype "passive"))
    )
    (net (code "69") (name "RCK") (class "Default")
      (node (ref "IC1") (pin "16") (pinfunction "PB2(SS/OC1B)_16") (pintype "bidirectional"))
      (node (ref "IC2") (pin "12") (pinfunction "RCK_12") (pintype "input"))
    )
    (net (code "70") (name "RST") (class "Default")
      (node (ref "IC1") (pin "1") (pinfunction "PC6(/RESET)_1") (pintype "bidirectional"))
      (node (ref "R1") (pin "1") (pinfunction "1_1") (pintype "passive"))
      (node (ref "SV6") (pin "5") (pinfunction "5_5") (pintype "passive"))
    )
    (net (code "71") (name "RX") (class "Default")
      (node (ref "IC1") (pin "2") (pinfunction "PD0(RXD)_2") (pintype "bidirectional"))
      (node (ref "IC11") (pin "1") (pinfunction "1_1") (pintype "passive"))
      (node (ref "IC11") (pin "2") (pinfunction "2_2") (pintype "passive"))
    )
    (net (code "72") (name "SCK") (class "Default")
      (node (ref "IC1") (pin "19") (pinfunction "PB5(SCK)_19") (pintype "bidirectional"))
      (node (ref "IC2") (pin "11") (pinfunction "SCK_11") (pintype "input"))
      (node (ref "SV6") (pin "3") (pinfunction "3_3") (pintype "passive"))
    )
    (net (code "73") (name "TX") (class "Default")
      (node (ref "IC1") (pin "3") (pinfunction "PD1(TXD)_3") (pintype "bidirectional"))
      (node (ref "IC10") (pin "5") (pinfunction "5_5") (pintype "passive"))
    )
    (net (code "74") (name "USB_RX") (class "Default")
      (node (ref "IC10") (pin "6") (pinfunction "6_6") (pintype "passive"))
      (node (ref "IC11") (pin "7") (pinfunction "7_7") (pintype "passive"))
    )
    (net (code "75") (name "VBAS") (class "Default")
      (node (ref "IC10") (pin "1") (pinfunction "1_1") (pintype "passive"))
      (node (ref "SV7") (pin "1") (pinfunction "1_1") (pintype "passive"))
    )
    (net (code "76") (name "VBIAS") (class "Default")
      (node (ref "C13") (pin "1") (pinfunction "1_1") (pintype "passive"))
      (node (ref "IC8") (pin "3") (pinfunction "3_3") (pintype "passive"))
      (node (ref "R21") (pin "1") (pinfunction "1_1") (pintype "passive"))
      (node (ref "R22") (pin "2") (pinfunction "2_2") (pintype "passive"))
    )
    (net (code "77") (name "VCC") (class "Default")
      (node (ref "C15") (pin "1") (pinfunction "1_1") (pintype "passive"))
      (node (ref "C16") (pin "1") (pinfunction "1_1") (pintype "passive"))
      (node (ref "C17") (pin "1") (pinfunction "1_1") (pintype "passive"))
      (node (ref "C18") (pin "1") (pinfunction "1_1") (pintype "passive"))
      (node (ref "C19") (pin "1") (pinfunction "1_1") (pintype "passive"))
      (node (ref "C20") (pin "1") (pinfunction "1_1") (pintype "passive"))
      (node (ref "C21") (pin "1") (pinfunction "1_1") (pintype "passive"))
      (node (ref "C23") (pin "+") (pinfunction "+_+") (pintype "passive"))
      (node (ref "C3") (pin "1") (pinfunction "1_1") (pintype "passive"))
      (node (ref "D3") (pin "A") (pinfunction "A_A") (pintype "passive"))
      (node (ref "IC1") (pin "20") (pinfunction "AVCC_20") (pintype "power_in"))
      (node (ref "IC1") (pin "7") (pinfunction "VCC_7") (pintype "power_in"))
      (node (ref "IC11") (pin "5") (pinfunction "5_5") (pintype "passive"))
      (node (ref "IC11") (pin "6") (pinfunction "6_6") (pintype "passive"))
      (node (ref "IC2") (pin "10") (pinfunction "SCL_10") (pintype "input"))
      (node (ref "IC3") (pin "4") (pinfunction "4_4") (pintype "passive"))
      (node (ref "IC4") (pin "4") (pinfunction "4_4") (pintype "passive"))
      (node (ref "IC5") (pin "4") (pinfunction "4_4") (pintype "passive"))
      (node (ref "IC6") (pin "16") (pinfunction "16_16") (pintype "passive"))
      (node (ref "IC7") (pin "8") (pinfunction "8_8") (pintype "passive"))
      (node (ref "IC8") (pin "8") (pinfunction "8_8") (pintype "passive"))
      (node (ref "IC9") (pin "7") (pinfunction "7_7") (pintype "passive"))
      (node (ref "QG1") (pin "8") (pinfunction "VCC_8") (pintype "power_in"))
      (node (ref "QG2") (pin "14") (pinfunction "VCC_14") (pintype "power_in"))
      (node (ref "R1") (pin "2") (pinfunction "2_2") (pintype "passive"))
      (node (ref "R21") (pin "2") (pinfunction "2_2") (pintype "passive"))
      (node (ref "R24") (pin "2") (pinfunction "2_2") (pintype "passive"))
      (node (ref "R25") (pin "2") (pinfunction "2_2") (pintype "passive"))
      (node (ref "R26") (pin "2") (pinfunction "2_2") (pintype "passive"))
      (node (ref "R27") (pin "2") (pinfunction "2_2") (pintype "passive"))
      (node (ref "R3") (pin "2") (pinfunction "2_2") (pintype "passive"))
      (node (ref "R30") (pin "2") (pinfunction "2_2") (pintype "passive"))
      (node (ref "R9") (pin "2") (pinfunction "2_2") (pintype "passive"))
      (node (ref "SV4") (pin "2") (pinfunction "2_2") (pintype "passive"))
      (node (ref "SV6") (pin "2") (pinfunction "2_2") (pintype "passive"))
    )
    (net (code "78") (name "unconnected-(IC1-PD2(INT0)-Pad4)") (class "Default")
      (node (ref "IC1") (pin "4") (pinfunction "PD2(INT0)_4") (pintype "bidirectional"))
    )
    (net (code "79") (name "unconnected-(IC1-PD3(INT1)-Pad5)") (class "Default")
      (node (ref "IC1") (pin "5") (pinfunction "PD3(INT1)_5") (pintype "bidirectional"))
    )
    (net (code "80") (name "unconnected-(IC2A-QH*-Pad9)") (class "Default")
      (node (ref "IC2") (pin "9") (pinfunction "QH*_9") (pintype "tri_state"))
    )
    (net (code "81") (name "unconnected-(IC3-Pad10)") (class "Default")
      (node (ref "IC3") (pin "10") (pinfunction "10_10") (pintype "passive"))
    )
    (net (code "82") (name "unconnected-(IC4-Pad10)") (class "Default")
      (node (ref "IC4") (pin "10") (pinfunction "10_10") (pintype "passive"))
    )
    (net (code "83") (name "unconnected-(IC5-Pad10)") (class "Default")
      (node (ref "IC5") (pin "10") (pinfunction "10_10") (pintype "passive"))
    )
    (net (code "84") (name "unconnected-(IC6-Pad9)") (class "Default")
      (node (ref "IC6") (pin "9") (pinfunction "9_9") (pintype "passive"))
    )
    (net (code "85") (name "unconnected-(IC7-Pad3)") (class "Default")
      (node (ref "IC7") (pin "3") (pinfunction "3_3") (pintype "passive"))
    )
    (net (code "86") (name "unconnected-(IC7-Pad4)") (class "Default")
      (node (ref "IC7") (pin "4") (pinfunction "4_4") (pintype "passive"))
    )
    (net (code "87") (name "unconnected-(IC7-Pad6)") (class "Default")
      (node (ref "IC7") (pin "6") (pinfunction "6_6") (pintype "passive"))
    )
    (net (code "88") (name "unconnected-(IC8-Pad5)") (class "Default")
      (node (ref "IC8") (pin "5") (pinfunction "5_5") (pintype "passive"))
    )
    (net (code "89") (name "unconnected-(IC8-Pad6)") (class "Default")
      (node (ref "IC8") (pin "6") (pinfunction "6_6") (pintype "passive"))
    )
    (net (code "90") (name "unconnected-(IC8-Pad7)") (class "Default")
      (node (ref "IC8") (pin "7") (pinfunction "7_7") (pintype "passive"))
    )
    (net (code "91") (name "unconnected-(IC9-Pad5)") (class "Default")
      (node (ref "IC9") (pin "5") (pinfunction "5_5") (pintype "passive"))
    )
    (net (code "92") (name "unconnected-(IC10-Pad4)") (class "Default")
      (node (ref "IC10") (pin "4") (pinfunction "4_4") (pintype "passive"))
    )
    (net (code "93") (name "unconnected-(IC10-Pad8)") (class "Default")
      (node (ref "IC10") (pin "8") (pinfunction "8_8") (pintype "passive"))
    )
    (net (code "94") (name "unconnected-(IC10-Pad9)") (class "Default")
      (node (ref "IC10") (pin "9") (pinfunction "9_9") (pintype "passive"))
    )
    (net (code "95") (name "unconnected-(IC10-Pad10)") (class "Default")
      (node (ref "IC10") (pin "10") (pinfunction "10_10") (pintype "passive"))
    )
    (net (code "96") (name "unconnected-(IC10-Pad11)") (class "Default")
      (node (ref "IC10") (pin "11") (pinfunction "11_11") (pintype "passive"))
    )
    (net (code "97") (name "unconnected-(QG1-TS-Pad1)") (class "Default")
      (node (ref "QG1") (pin "1") (pinfunction "TS_1") (pintype "passive"))
    )
    (net (code "98") (name "unconnected-(QG2-TS-Pad1)") (class "Default")
      (node (ref "QG2") (pin "1") (pinfunction "TS_1") (pintype "passive"))
    )
    (net (code "99") (name "unconnected-(SV1-Pad1)") (class "Default")
      (node (ref "SV1") (pin "1") (pinfunction "1_1") (pintype "passive"))
    )
    (net (code "100") (name "unconnected-(SV1-Pad2)") (class "Default")
      (node (ref "SV1") (pin "2") (pinfunction "2_2") (pintype "passive"))
    )
    (net (code "101") (name "unconnected-(SV1-Pad3)") (class "Default")
      (node (ref "SV1") (pin "3") (pinfunction "3_3") (pintype "passive"))
    )
  )
)
